# ROwen_Power.net
KiCad netlist of a schematic drawn in EAGLE
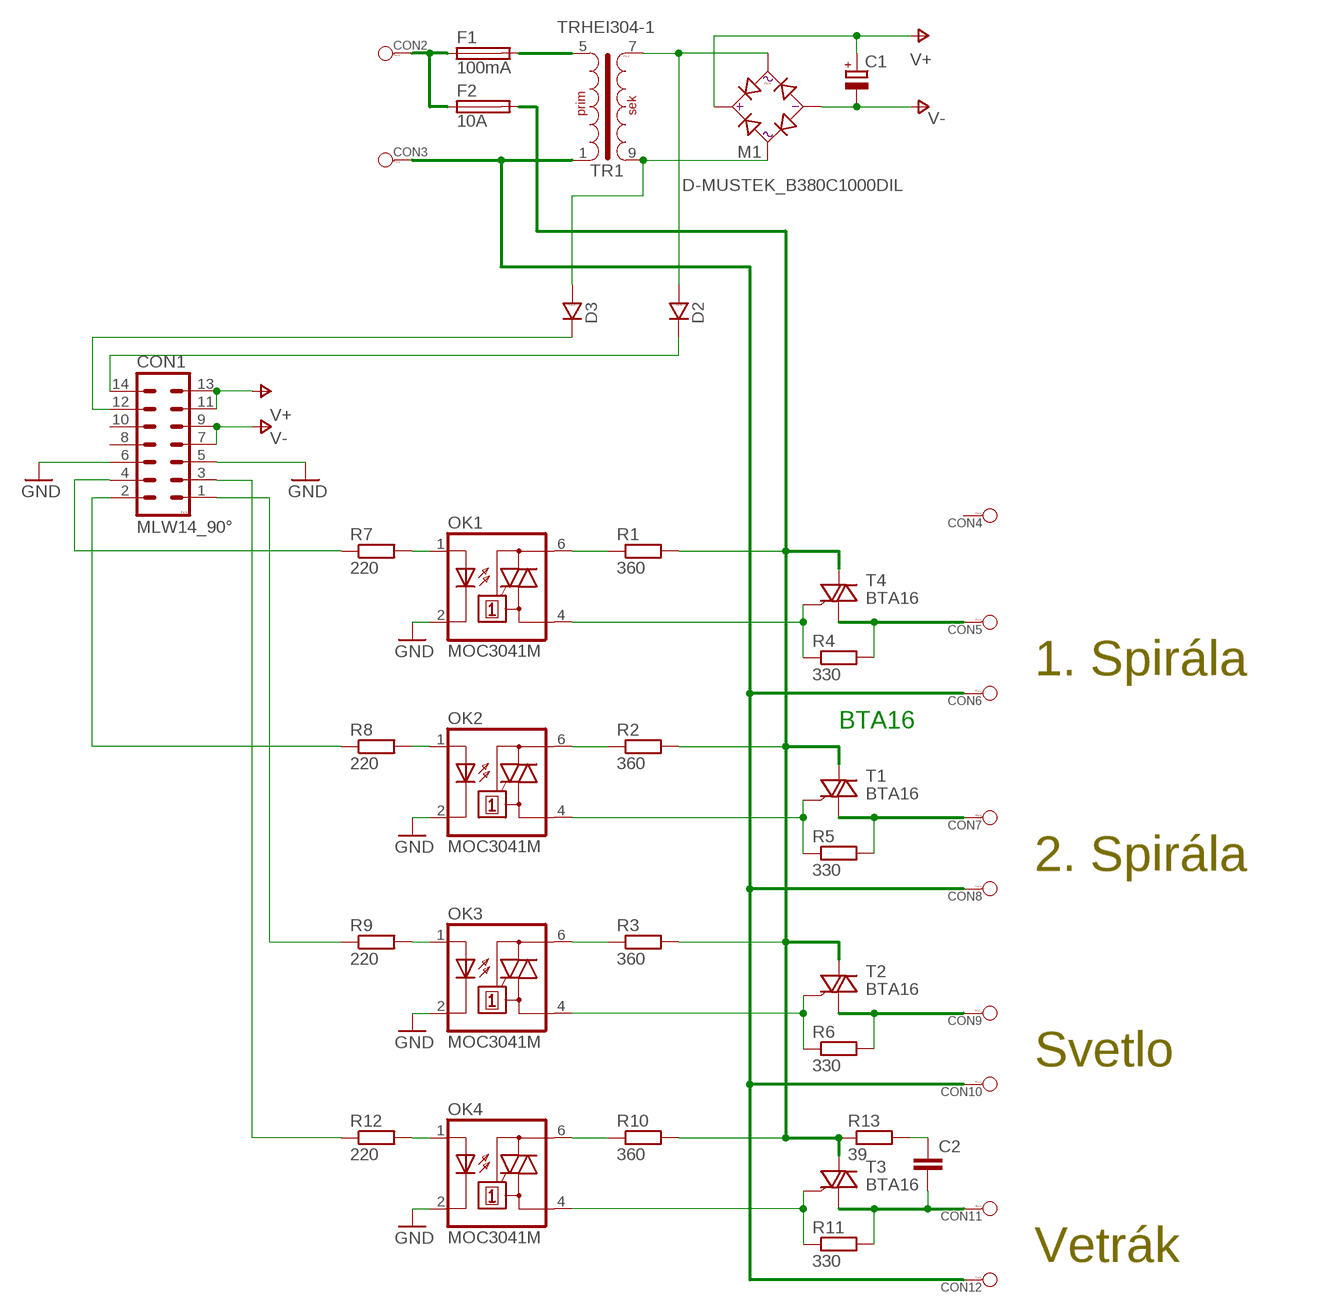
[diagram p0: schematic, sheet 1]

(export (version "E")
  (design (tool "Eeschema 10.0.6"))
  (components
    (comp (ref "C1")
      (value "CPOL-EUE3.5-10")
      (footprint "eagle-import:E3,5-10")
      (libsource (lib "eagle-import") (part "CPOL-EUE3.5-10"))
    )
    (comp (ref "C2")
      (value "C-EU050-055X075")
      (footprint "eagle-import:C050-055X075")
      (libsource (lib "eagle-import") (part "C-EU050-055X075"))
    )
    (comp (ref "CON1")
      (value "MLW14_90°")
      (footprint "eagle-import:MLW14A")
      (libsource (lib "eagle-import") (part "MLW14_90°"))
    )
    (comp (ref "CON2")
      (value "WAGO256")
      (footprint "eagle-import:WAGO256")
      (libsource (lib "eagle-import") (part "WAGO256"))
    )
    (comp (ref "CON3")
      (value "WAGO256")
      (footprint "eagle-import:WAGO256")
      (libsource (lib "eagle-import") (part "WAGO256"))
    )
    (comp (ref "CON4")
      (value "WAGO256")
      (footprint "eagle-import:WAGO256")
      (libsource (lib "eagle-import") (part "WAGO256"))
    )
    (comp (ref "CON5")
      (value "WAGO256")
      (footprint "eagle-import:WAGO256")
      (libsource (lib "eagle-import") (part "WAGO256"))
    )
    (comp (ref "CON6")
      (value "WAGO256")
      (footprint "eagle-import:WAGO256")
      (libsource (lib "eagle-import") (part "WAGO256"))
    )
    (comp (ref "CON7")
      (value "WAGO256")
      (footprint "eagle-import:WAGO256")
      (libsource (lib "eagle-import") (part "WAGO256"))
    )
    (comp (ref "CON8")
      (value "WAGO256")
      (footprint "eagle-import:WAGO256")
      (libsource (lib "eagle-import") (part "WAGO256"))
    )
    (comp (ref "CON9")
      (value "WAGO256")
      (footprint "eagle-import:WAGO256")
      (libsource (lib "eagle-import") (part "WAGO256"))
    )
    (comp (ref "CON10")
      (value "WAGO256")
      (footprint "eagle-import:WAGO256")
      (libsource (lib "eagle-import") (part "WAGO256"))
    )
    (comp (ref "CON11")
      (value "WAGO256")
      (footprint "eagle-import:WAGO256")
      (libsource (lib "eagle-import") (part "WAGO256"))
    )
    (comp (ref "CON12")
      (value "WAGO256")
      (footprint "eagle-import:WAGO256")
      (libsource (lib "eagle-import") (part "WAGO256"))
    )
    (comp (ref "D2")
      (value "D_10")
      (footprint "eagle-import:DO41")
      (libsource (lib "eagle-import") (part "D_10"))
    )
    (comp (ref "D3")
      (value "D_10")
      (footprint "eagle-import:DO41")
      (libsource (lib "eagle-import") (part "D_10"))
    )
    (comp (ref "F1")
      (value "100mA")
      (footprint "eagle-import:SH22,5A")
      (fields (field (name "MPN") "0031.7701.11"))
      (libsource (lib "eagle-import") (part "SH22,5A"))
    )
    (comp (ref "F2")
      (value "10A")
      (footprint "eagle-import:SH22,5A")
      (fields (field (name "MPN") "0031.7701.11"))
      (libsource (lib "eagle-import") (part "SH22,5A"))
    )
    (comp (ref "M1")
      (value "D-MUSTEK_B380C1000DIL")
      (footprint "eagle-import:DM_DB1")
      (libsource (lib "eagle-import") (part "D-MUSTEK_B380C1000DIL"))
    )
    (comp (ref "OK1")
      (value "MOC3041M")
      (footprint "eagle-import:DIL06")
      (fields (field (name "MF") "FAIRCHILD SEMICONDUCTOR"))
      (libsource (lib "eagle-import") (part "MOC3041M"))
    )
    (comp (ref "OK2")
      (value "MOC3041M")
      (footprint "eagle-import:DIL06")
      (fields (field (name "MF") "FAIRCHILD SEMICONDUCTOR"))
      (libsource (lib "eagle-import") (part "MOC3041M"))
    )
    (comp (ref "OK3")
      (value "MOC3041M")
      (footprint "eagle-import:DIL06")
      (fields (field (name "MF") "FAIRCHILD SEMICONDUCTOR"))
      (libsource (lib "eagle-import") (part "MOC3041M"))
    )
    (comp (ref "OK4")
      (value "MOC3041M")
      (footprint "eagle-import:DIL06")
      (fields (field (name "MF") "FAIRCHILD SEMICONDUCTOR"))
      (libsource (lib "eagle-import") (part "MOC3041M"))
    )
    (comp (ref "R1")
      (value "360")
      (footprint "eagle-import:0207_10")
      (libsource (lib "eagle-import") (part "R-EU_0207/10"))
    )
    (comp (ref "R2")
      (value "360")
      (footprint "eagle-import:0207_10")
      (libsource (lib "eagle-import") (part "R-EU_0207/10"))
    )
    (comp (ref "R3")
      (value "360")
      (footprint "eagle-import:0207_10")
      (libsource (lib "eagle-import") (part "R-EU_0207/10"))
    )
    (comp (ref "R4")
      (value "330")
      (footprint "eagle-import:0207_10")
      (libsource (lib "eagle-import") (part "R-EU_0207/10"))
    )
    (comp (ref "R5")
      (value "330")
      (footprint "eagle-import:0207_10")
      (libsource (lib "eagle-import") (part "R-EU_0207/10"))
    )
    (comp (ref "R6")
      (value "330")
      (footprint "eagle-import:0207_10")
      (libsource (lib "eagle-import") (part "R-EU_0207/10"))
    )
    (comp (ref "R7")
      (value "220")
      (footprint "eagle-import:0207_10")
      (libsource (lib "eagle-import") (part "R-EU_0207/10"))
    )
    (comp (ref "R8")
      (value "220")
      (footprint "eagle-import:0207_10")
      (libsource (lib "eagle-import") (part "R-EU_0207/10"))
    )
    (comp (ref "R9")
      (value "220")
      (footprint "eagle-import:0207_10")
      (libsource (lib "eagle-import") (part "R-EU_0207/10"))
    )
    (comp (ref "R10")
      (value "360")
      (footprint "eagle-import:0207_10")
      (libsource (lib "eagle-import") (part "R-EU_0207/10"))
    )
    (comp (ref "R11")
      (value "330")
      (footprint "eagle-import:0207_10")
      (libsource (lib "eagle-import") (part "R-EU_0207/10"))
    )
    (comp (ref "R12")
      (value "220")
      (footprint "eagle-import:0207_10")
      (libsource (lib "eagle-import") (part "R-EU_0207/10"))
    )
    (comp (ref "R13")
      (value "39")
      (footprint "eagle-import:0309_12")
      (libsource (lib "eagle-import") (part "R-EU_0309/12"))
    )
    (comp (ref "T1")
      (value "BTA16")
      (footprint "eagle-import:TO220")
      (libsource (lib "eagle-import") (part "BTA16"))
    )
    (comp (ref "T2")
      (value "BTA16")
      (footprint "eagle-import:TO220")
      (libsource (lib "eagle-import") (part "BTA16"))
    )
    (comp (ref "T3")
      (value "BTA16")
      (footprint "eagle-import:TO220")
      (libsource (lib "eagle-import") (part "BTA16"))
    )
    (comp (ref "T4")
      (value "BTA16")
      (footprint "eagle-import:TO220")
      (libsource (lib "eagle-import") (part "BTA16"))
    )
    (comp (ref "TR1")
      (value "TRHEI304-1")
      (footprint "eagle-import:TRHEI304")
      (libsource (lib "eagle-import") (part "TRHEI304-1"))
    )
  )
  (nets
    (net (code "1") (name "GND") (class "Default")
      (node (ref "CON1") (pin "5") (pinfunction "5_5") (pintype "passive"))
      (node (ref "CON1") (pin "6") (pinfunction "6_6") (pintype "passive"))
      (node (ref "OK1") (pin "2") (pinfunction "C_2") (pintype "passive"))
      (node (ref "OK2") (pin "2") (pinfunction "C_2") (pintype "passive"))
      (node (ref "OK3") (pin "2") (pinfunction "C_2") (pintype "passive"))
      (node (ref "OK4") (pin "2") (pinfunction "C_2") (pintype "passive"))
    )
    (net (code "2") (name "Net-(C2-Pad1)") (class "Default")
      (node (ref "C2") (pin "1") (pinfunction "1_1") (pintype "passive"))
      (node (ref "R13") (pin "2") (pinfunction "2_2") (pintype "passive"))
    )
    (net (code "3") (name "Net-(CON1-Pad1)") (class "Default")
      (node (ref "CON1") (pin "1") (pinfunction "1_1") (pintype "passive"))
      (node (ref "R9") (pin "1") (pinfunction "1_1") (pintype "passive"))
    )
    (net (code "4") (name "Net-(CON1-Pad2)") (class "Default")
      (node (ref "CON1") (pin "2") (pinfunction "2_2") (pintype "passive"))
      (node (ref "R8") (pin "1") (pinfunction "1_1") (pintype "passive"))
    )
    (net (code "5") (name "Net-(CON1-Pad3)") (class "Default")
      (node (ref "CON1") (pin "3") (pinfunction "3_3") (pintype "passive"))
      (node (ref "R12") (pin "1") (pinfunction "1_1") (pintype "passive"))
    )
    (net (code "6") (name "Net-(CON1-Pad4)") (class "Default")
      (node (ref "CON1") (pin "4") (pinfunction "4_4") (pintype "passive"))
      (node (ref "R7") (pin "1") (pinfunction "1_1") (pintype "passive"))
    )
    (net (code "7") (name "Net-(CON1-Pad12)") (class "Default")
      (node (ref "CON1") (pin "12") (pinfunction "12_12") (pintype "passive"))
      (node (ref "D3") (pin "K") (pinfunction "K_K") (pintype "passive"))
    )
    (net (code "8") (name "Net-(CON1-Pad14)") (class "Default")
      (node (ref "CON1") (pin "14") (pinfunction "14_14") (pintype "passive"))
      (node (ref "D2") (pin "K") (pinfunction "K_K") (pintype "passive"))
    )
    (net (code "9") (name "Net-(CON2-Pad1)") (class "Default")
      (node (ref "CON2") (pin "1") (pinfunction "1_1") (pintype "passive"))
      (node (ref "F1") (pin "1") (pinfunction "1_1") (pintype "passive"))
      (node (ref "F2") (pin "1") (pinfunction "1_1") (pintype "passive"))
    )
    (net (code "10") (name "Net-(OK1-A)") (class "Default")
      (node (ref "OK1") (pin "1") (pinfunction "A_1") (pintype "passive"))
      (node (ref "R7") (pin "2") (pinfunction "2_2") (pintype "passive"))
    )
    (net (code "11") (name "Net-(OK1-A1)") (class "Default")
      (node (ref "OK1") (pin "4") (pinfunction "A1_4") (pintype "passive"))
      (node (ref "R4") (pin "1") (pinfunction "1_1") (pintype "passive"))
      (node (ref "T4") (pin "G") (pinfunction "G_G") (pintype "passive"))
    )
    (net (code "12") (name "Net-(OK1-A2)") (class "Default")
      (node (ref "OK1") (pin "6") (pinfunction "A2_6") (pintype "passive"))
      (node (ref "R1") (pin "1") (pinfunction "1_1") (pintype "passive"))
    )
    (net (code "13") (name "Net-(OK2-A)") (class "Default")
      (node (ref "OK2") (pin "1") (pinfunction "A_1") (pintype "passive"))
      (node (ref "R8") (pin "2") (pinfunction "2_2") (pintype "passive"))
    )
    (net (code "14") (name "Net-(OK2-A1)") (class "Default")
      (node (ref "OK2") (pin "4") (pinfunction "A1_4") (pintype "passive"))
      (node (ref "R5") (pin "1") (pinfunction "1_1") (pintype "passive"))
      (node (ref "T1") (pin "G") (pinfunction "G_G") (pintype "passive"))
    )
    (net (code "15") (name "Net-(OK2-A2)") (class "Default")
      (node (ref "OK2") (pin "6") (pinfunction "A2_6") (pintype "passive"))
      (node (ref "R2") (pin "1") (pinfunction "1_1") (pintype "passive"))
    )
    (net (code "16") (name "Net-(OK3-A)") (class "Default")
      (node (ref "OK3") (pin "1") (pinfunction "A_1") (pintype "passive"))
      (node (ref "R9") (pin "2") (pinfunction "2_2") (pintype "passive"))
    )
    (net (code "17") (name "Net-(OK3-A1)") (class "Default")
      (node (ref "OK3") (pin "4") (pinfunction "A1_4") (pintype "passive"))
      (node (ref "R6") (pin "1") (pinfunction "1_1") (pintype "passive"))
      (node (ref "T2") (pin "G") (pinfunction "G_G") (pintype "passive"))
    )
    (net (code "18") (name "Net-(OK3-A2)") (class "Default")
      (node (ref "OK3") (pin "6") (pinfunction "A2_6") (pintype "passive"))
      (node (ref "R3") (pin "1") (pinfunction "1_1") (pintype "passive"))
    )
    (net (code "19") (name "Net-(OK4-A)") (class "Default")
      (node (ref "OK4") (pin "1") (pinfunction "A_1") (pintype "passive"))
      (node (ref "R12") (pin "2") (pinfunction "2_2") (pintype "passive"))
    )
    (net (code "20") (name "Net-(OK4-A1)") (class "Default")
      (node (ref "OK4") (pin "4") (pinfunction "A1_4") (pintype "passive"))
      (node (ref "R11") (pin "1") (pinfunction "1_1") (pintype "passive"))
      (node (ref "T3") (pin "G") (pinfunction "G_G") (pintype "passive"))
    )
    (net (code "21") (name "Net-(OK4-A2)") (class "Default")
      (node (ref "OK4") (pin "6") (pinfunction "A2_6") (pintype "passive"))
      (node (ref "R10") (pin "1") (pinfunction "1_1") (pintype "passive"))
    )
    (net (code "22") (name "Net-(T1-A1)") (class "Default")
      (node (ref "CON7") (pin "1") (pinfunction "1_1") (pintype "passive"))
      (node (ref "R5") (pin "2") (pinfunction "2_2") (pintype "passive"))
      (node (ref "T1") (pin "T1") (pinfunction "A1_T1") (pintype "passive"))
    )
    (net (code "23") (name "Net-(T1-A2)") (class "Default")
      (node (ref "F2") (pin "2") (pinfunction "2_2") (pintype "passive"))
      (node (ref "R1") (pin "2") (pinfunction "2_2") (pintype "passive"))
      (node (ref "R10") (pin "2") (pinfunction "2_2") (pintype "passive"))
      (node (ref "R13") (pin "1") (pinfunction "1_1") (pintype "passive"))
      (node (ref "R2") (pin "2") (pinfunction "2_2") (pintype "passive"))
      (node (ref "R3") (pin "2") (pinfunction "2_2") (pintype "passive"))
      (node (ref "T1") (pin "T2") (pinfunction "A2_T2") (pintype "passive"))
      (node (ref "T2") (pin "T2") (pinfunction "A2_T2") (pintype "passive"))
      (node (ref "T3") (pin "T2") (pinfunction "A2_T2") (pintype "passive"))
      (node (ref "T4") (pin "T2") (pinfunction "A2_T2") (pintype "passive"))
    )
    (net (code "24") (name "Net-(T2-A1)") (class "Default")
      (node (ref "CON9") (pin "1") (pinfunction "1_1") (pintype "passive"))
      (node (ref "R6") (pin "2") (pinfunction "2_2") (pintype "passive"))
      (node (ref "T2") (pin "T1") (pinfunction "A1_T1") (pintype "passive"))
    )
    (net (code "25") (name "Net-(T3-A1)") (class "Default")
      (node (ref "C2") (pin "2") (pinfunction "2_2") (pintype "passive"))
      (node (ref "CON11") (pin "1") (pinfunction "1_1") (pintype "passive"))
      (node (ref "R11") (pin "2") (pinfunction "2_2") (pintype "passive"))
      (node (ref "T3") (pin "T1") (pinfunction "A1_T1") (pintype "passive"))
    )
    (net (code "26") (name "Net-(T4-A1)") (class "Default")
      (node (ref "CON5") (pin "1") (pinfunction "1_1") (pintype "passive"))
      (node (ref "R4") (pin "2") (pinfunction "2_2") (pintype "passive"))
      (node (ref "T4") (pin "T1") (pinfunction "A1_T1") (pintype "passive"))
    )
    (net (code "27") (name "Net-(TR1-P1)") (class "Default")
      (node (ref "CON10") (pin "1") (pinfunction "1_1") (pintype "passive"))
      (node (ref "CON12") (pin "1") (pinfunction "1_1") (pintype "passive"))
      (node (ref "CON3") (pin "1") (pinfunction "1_1") (pintype "passive"))
      (node (ref "CON6") (pin "1") (pinfunction "1_1") (pintype "passive"))
      (node (ref "CON8") (pin "1") (pinfunction "1_1") (pintype "passive"))
      (node (ref "TR1") (pin "1") (pinfunction "P1_1") (pintype "passive"))
    )
    (net (code "28") (name "Net-(TR1-P2)") (class "Default")
      (node (ref "F1") (pin "2") (pinfunction "2_2") (pintype "passive"))
      (node (ref "TR1") (pin "5") (pinfunction "P2_5") (pintype "passive"))
    )
    (net (code "29") (name "Net-(TR1-S1)") (class "Default")
      (node (ref "D2") (pin "A") (pinfunction "A_A") (pintype "passive"))
      (node (ref "M1") (pin "AC2") (pinfunction "AC2_AC2") (pintype "passive"))
      (node (ref "TR1") (pin "7") (pinfunction "S1_7") (pintype "passive"))
    )
    (net (code "30") (name "Net-(TR1-S2)") (class "Default")
      (node (ref "D3") (pin "A") (pinfunction "A_A") (pintype "passive"))
      (node (ref "M1") (pin "AC1") (pinfunction "AC1_AC1") (pintype "passive"))
      (node (ref "TR1") (pin "9") (pinfunction "S2_9") (pintype "passive"))
    )
    (net (code "31") (name "V+") (class "Default")
      (node (ref "C1") (pin "+") (pinfunction "+_+") (pintype "passive"))
      (node (ref "CON1") (pin "11") (pinfunction "11_11") (pintype "passive"))
      (node (ref "CON1") (pin "13") (pinfunction "13_13") (pintype "passive"))
      (node (ref "M1") (pin "+") (pinfunction "+_+") (pintype "passive"))
    )
    (net (code "32") (name "V-") (class "Default")
      (node (ref "C1") (pin "-") (pinfunction "-_-") (pintype "passive"))
      (node (ref "CON1") (pin "7") (pinfunction "7_7") (pintype "passive"))
      (node (ref "CON1") (pin "9") (pinfunction "9_9") (pintype "passive"))
      (node (ref "M1") (pin "-") (pinfunction "-_-") (pintype "passive"))
    )
    (net (code "33") (name "unconnected-(CON1-Pad8)") (class "Default")
      (node (ref "CON1") (pin "8") (pinfunction "8_8") (pintype "passive"))
    )
    (net (code "34") (name "unconnected-(CON1-Pad10)") (class "Default")
      (node (ref "CON1") (pin "10") (pinfunction "10_10") (pintype "passive"))
    )
    (net (code "35") (name "unconnected-(CON4-Pad1)") (class "Default")
      (node (ref "CON4") (pin "1") (pinfunction "1_1") (pintype "passive"))
    )
  )
)
